# Display.net
KiCad netlist of a schematic drawn in Altium Designer
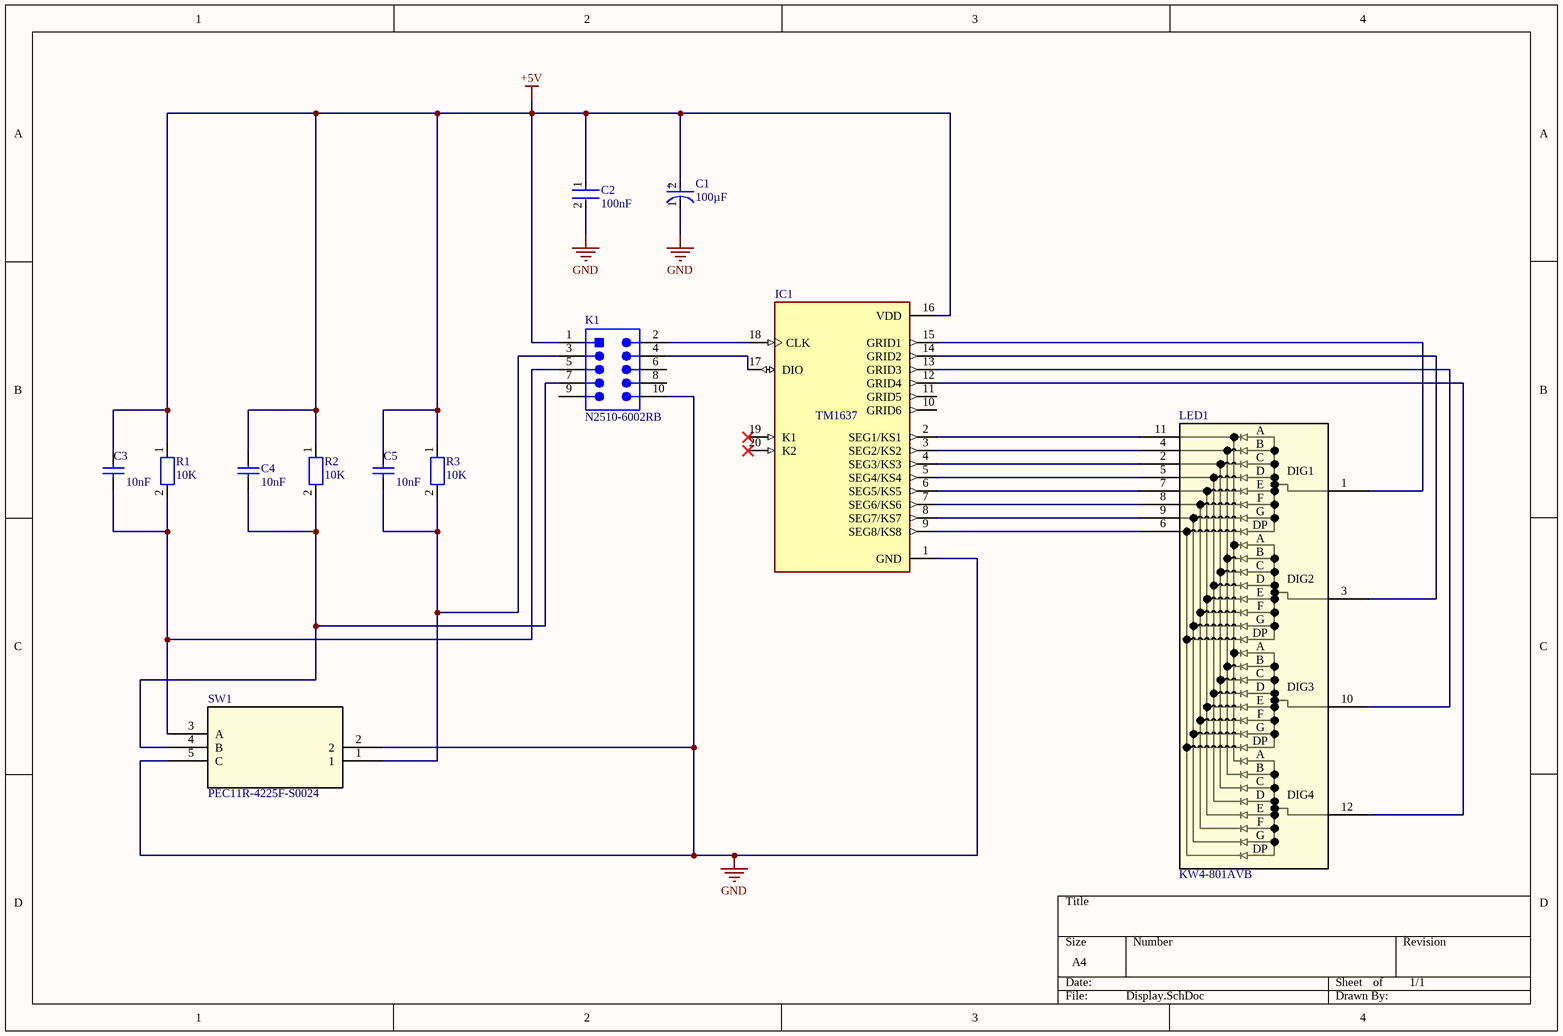
[diagram p0: Display.SchDoc]

(export (version "E")
  (design (tool "Eeschema 10.0.6"))
  (components
    (comp (ref "C1")
      (value "100µF")
      (footprint "Cap 50V 100µF 8X11")
      (description "Aluminum Electrolytic Capacitors (Radial Lead Type) AEC-Q200 Qualified 100uF ±20% 50V")
      (fields (field (name "VOLTAGE") "50V") (field (name "TOLERANCE") "20%"))
      (libsource (lib "soldeerstation") (part "Cap 50V 100µF 8x11"))
    )
    (comp (ref "C2")
      (value "100nF")
      (footprint "cap 50V 100nF A")
      (description "Chip Multilayer Ceramic Capacitors for Automotive, 0805, 0.10uF, X7R, 15%, 10%, 50V, Grade 1")
      (fields (field (name "TOLERANCE") "10%"))
      (libsource (lib "soldeerstation") (part "cap 50V 100nF"))
    )
    (comp (ref "C3")
      (value "10nF")
      (footprint "cap 10nF X7R 50V LL")
      (fields (field (name "PART NUMBER") "VJ0805Y103KXACW1BC") (field (name "MANUFACTURER") "Vitramon"))
      (libsource (lib "soldeerstation") (part "cap 10nF X7R 50V"))
    )
    (comp (ref "C4")
      (value "10nF")
      (footprint "cap 10nF X7R 50V LL")
      (fields (field (name "PART NUMBER") "VJ0805Y103KXACW1BC") (field (name "MANUFACTURER") "Vitramon"))
      (libsource (lib "soldeerstation") (part "cap 10nF X7R 50V"))
    )
    (comp (ref "C5")
      (value "10nF")
      (footprint "cap 10nF X7R 50V LL")
      (fields (field (name "PART NUMBER") "VJ0805Y103KXACW1BC") (field (name "MANUFACTURER") "Vitramon"))
      (libsource (lib "soldeerstation") (part "cap 10nF X7R 50V"))
    )
    (comp (ref "IC1")
      (value "TM1637")
      (footprint "TM1637")
      (description "LED Drive Control Special Circuit")
      (fields (field (name "MF") "Titan Micro Electronics"))
      (libsource (lib "soldeerstation") (part "TM1637"))
    )
    (comp (ref "K1")
      (value "N2510-6002RB")
      (footprint "boxheader")
      (fields (field (name "PARTNUMBER") "N2510") (field (name "MANUFACTURER") "3M"))
      (libsource (lib "soldeerstation") (part "boxheader"))
    )
    (comp (ref "LED1")
      (value "KW4-801AVB")
      (footprint "KW4801AVB")
      (description "No Description Available")
      (fields (field (name "COPYRIGHT") "Copyright (C) 2023 Ultra Librarian. All rights reserved."))
      (libsource (lib "soldeerstation") (part "KW4-801AVB"))
    )
    (comp (ref "R1")
      (value "10K")
      (footprint "Weerstand 10k ohm")
      (description "RES Thick Film, 10kΩ, 1%, 0.125W, 100ppm/°C, 0805")
      (fields (field (name "TOLERANCE") "1%"))
      (libsource (lib "soldeerstation") (part "Weerstand 10K ohm"))
    )
    (comp (ref "R2")
      (value "10K")
      (footprint "Weerstand 10k ohm")
      (description "RES Thick Film, 10kΩ, 1%, 0.125W, 100ppm/°C, 0805")
      (fields (field (name "TOLERANCE") "1%"))
      (libsource (lib "soldeerstation") (part "Weerstand 10K ohm"))
    )
    (comp (ref "R3")
      (value "10K")
      (footprint "Weerstand 10k ohm")
      (description "RES Thick Film, 10kΩ, 1%, 0.125W, 100ppm/°C, 0805")
      (fields (field (name "TOLERANCE") "1%"))
      (libsource (lib "soldeerstation") (part "Weerstand 10K ohm"))
    )
    (comp (ref "SW1")
      (value "PEC11R-4225F-S0024")
      (footprint "SW5_PEC11R-4225F-S0024_BRN")
      (description "No Description Available")
      (fields (field (name "COPYRIGHT") "Copyright (C) 2023 Ultra Librarian. All rights reserved."))
      (libsource (lib "soldeerstation") (part "PEC11R-4225F-S0024"))
    )
  )
  (nets
    (net (code "1") (name "+5V") (class "Default")
      (node (ref "C1") (pin "2") (pinfunction "A_2") (pintype "passive"))
      (node (ref "C2") (pin "1") (pinfunction "1_1") (pintype "passive"))
      (node (ref "C3") (pin "2") (pinfunction "2_2") (pintype "passive"))
      (node (ref "C4") (pin "2") (pinfunction "2_2") (pintype "passive"))
      (node (ref "C5") (pin "2") (pinfunction "2_2") (pintype "passive"))
      (node (ref "IC1") (pin "16") (pinfunction "VDD_16") (pintype "power_in"))
      (node (ref "K1") (pin "1") (pinfunction "1_1") (pintype "passive"))
      (node (ref "R1") (pin "1") (pinfunction "1_1") (pintype "passive"))
      (node (ref "R2") (pin "1") (pinfunction "1_1") (pintype "passive"))
      (node (ref "R3") (pin "1") (pinfunction "1_1") (pintype "passive"))
    )
    (net (code "2") (name "GND") (class "Default")
      (node (ref "C1") (pin "1") (pinfunction "C_1") (pintype "passive"))
      (node (ref "C2") (pin "2") (pinfunction "2_2") (pintype "passive"))
      (node (ref "IC1") (pin "1") (pinfunction "GND_1") (pintype "power_in"))
      (node (ref "K1") (pin "10") (pinfunction "10_10") (pintype "passive"))
      (node (ref "SW1") (pin "2") (pinfunction "2_2") (pintype "passive"))
      (node (ref "SW1") (pin "5") (pinfunction "C_5") (pintype "passive"))
    )
    (net (code "3") (name "Net-(C5-Pad1)") (class "Default")
      (node (ref "C5") (pin "1") (pinfunction "1_1") (pintype "passive"))
      (node (ref "K1") (pin "3") (pinfunction "3_3") (pintype "passive"))
      (node (ref "R3") (pin "2") (pinfunction "2_2") (pintype "passive"))
      (node (ref "SW1") (pin "1") (pinfunction "1_1") (pintype "passive"))
    )
    (net (code "4") (name "Net-(IC1-CLK)") (class "Default")
      (node (ref "IC1") (pin "18") (pinfunction "CLK_18") (pintype "input"))
      (node (ref "K1") (pin "2") (pinfunction "2_2") (pintype "passive"))
    )
    (net (code "5") (name "Net-(IC1-DIO)") (class "Default")
      (node (ref "IC1") (pin "17") (pinfunction "DIO_17") (pintype "bidirectional"))
      (node (ref "K1") (pin "4") (pinfunction "4_4") (pintype "passive"))
    )
    (net (code "6") (name "Net-(IC1-GRID1)") (class "Default")
      (node (ref "IC1") (pin "15") (pinfunction "GRID1_15") (pintype "output"))
      (node (ref "LED1") (pin "1") (pinfunction "COMMON_ANODE_1_1") (pintype "passive"))
    )
    (net (code "7") (name "Net-(IC1-GRID2)") (class "Default")
      (node (ref "IC1") (pin "14") (pinfunction "GRID2_14") (pintype "output"))
      (node (ref "LED1") (pin "3") (pinfunction "COMMON_ANODE_2_3") (pintype "passive"))
    )
    (net (code "8") (name "Net-(IC1-GRID3)") (class "Default")
      (node (ref "IC1") (pin "13") (pinfunction "GRID3_13") (pintype "output"))
      (node (ref "LED1") (pin "10") (pinfunction "COMMON_ANODE_3_10") (pintype "passive"))
    )
    (net (code "9") (name "Net-(IC1-GRID4)") (class "Default")
      (node (ref "IC1") (pin "12") (pinfunction "GRID4_12") (pintype "output"))
      (node (ref "LED1") (pin "12") (pinfunction "COMMON_ANODE_4_12") (pintype "passive"))
    )
    (net (code "10") (name "Net-(IC1-SEG1{slash}KS1)") (class "Default")
      (node (ref "IC1") (pin "2") (pinfunction "SEG1/KS1_2") (pintype "output"))
      (node (ref "LED1") (pin "11") (pinfunction "CATHODE_A_11") (pintype "passive"))
    )
    (net (code "11") (name "Net-(IC1-SEG2{slash}KS2)") (class "Default")
      (node (ref "IC1") (pin "3") (pinfunction "SEG2/KS2_3") (pintype "output"))
      (node (ref "LED1") (pin "4") (pinfunction "CATHODE_B_4") (pintype "passive"))
    )
    (net (code "12") (name "Net-(IC1-SEG3{slash}KS3)") (class "Default")
      (node (ref "IC1") (pin "4") (pinfunction "SEG3/KS3_4") (pintype "output"))
      (node (ref "LED1") (pin "2") (pinfunction "CATHODE_C_2") (pintype "passive"))
    )
    (net (code "13") (name "Net-(IC1-SEG4{slash}KS4)") (class "Default")
      (node (ref "IC1") (pin "5") (pinfunction "SEG4/KS4_5") (pintype "output"))
      (node (ref "LED1") (pin "5") (pinfunction "CATHODE_D_5") (pintype "passive"))
    )
    (net (code "14") (name "Net-(IC1-SEG5{slash}KS5)") (class "Default")
      (node (ref "IC1") (pin "6") (pinfunction "SEG5/KS5_6") (pintype "output"))
      (node (ref "LED1") (pin "7") (pinfunction "CATHODE_E_7") (pintype "passive"))
    )
    (net (code "15") (name "Net-(IC1-SEG6{slash}KS6)") (class "Default")
      (node (ref "IC1") (pin "7") (pinfunction "SEG6/KS6_7") (pintype "output"))
      (node (ref "LED1") (pin "8") (pinfunction "CATHODE_F_8") (pintype "passive"))
    )
    (net (code "16") (name "Net-(IC1-SEG7{slash}KS7)") (class "Default")
      (node (ref "IC1") (pin "8") (pinfunction "SEG7/KS7_8") (pintype "output"))
      (node (ref "LED1") (pin "9") (pinfunction "CATHODE_G_9") (pintype "passive"))
    )
    (net (code "17") (name "Net-(IC1-SEG8{slash}KS8)") (class "Default")
      (node (ref "IC1") (pin "9") (pinfunction "SEG8/KS8_9") (pintype "output"))
      (node (ref "LED1") (pin "6") (pinfunction "CATHODE_DP_6") (pintype "passive"))
    )
    (net (code "18") (name "Net-(SW1-A)") (class "Default")
      (node (ref "C3") (pin "1") (pinfunction "1_1") (pintype "passive"))
      (node (ref "K1") (pin "5") (pinfunction "5_5") (pintype "passive"))
      (node (ref "R1") (pin "2") (pinfunction "2_2") (pintype "passive"))
      (node (ref "SW1") (pin "3") (pinfunction "A_3") (pintype "passive"))
    )
    (net (code "19") (name "Net-(SW1-B)") (class "Default")
      (node (ref "C4") (pin "1") (pinfunction "1_1") (pintype "passive"))
      (node (ref "K1") (pin "7") (pinfunction "7_7") (pintype "passive"))
      (node (ref "R2") (pin "2") (pinfunction "2_2") (pintype "passive"))
      (node (ref "SW1") (pin "4") (pinfunction "B_4") (pintype "passive"))
    )
    (net (code "20") (name "unconnected-(IC1-GRID5-Pad11)") (class "Default")
      (node (ref "IC1") (pin "11") (pinfunction "GRID5_11") (pintype "output"))
    )
    (net (code "21") (name "unconnected-(IC1-GRID6-Pad10)") (class "Default")
      (node (ref "IC1") (pin "10") (pinfunction "GRID6_10") (pintype "output"))
    )
    (net (code "22") (name "unconnected-(IC1-K1-Pad19)") (class "Default")
      (node (ref "IC1") (pin "19") (pinfunction "K1_19") (pintype "input+no_connect"))
    )
    (net (code "23") (name "unconnected-(IC1-K2-Pad20)") (class "Default")
      (node (ref "IC1") (pin "20") (pinfunction "K2_20") (pintype "input+no_connect"))
    )
    (net (code "24") (name "unconnected-(K1-Pad6)") (class "Default")
      (node (ref "K1") (pin "6") (pinfunction "6_6") (pintype "passive"))
    )
    (net (code "25") (name "unconnected-(K1-Pad8)") (class "Default")
      (node (ref "K1") (pin "8") (pinfunction "8_8") (pintype "passive"))
    )
    (net (code "26") (name "unconnected-(K1-Pad9)") (class "Default")
      (node (ref "K1") (pin "9") (pinfunction "9_9") (pintype "passive"))
    )
  )
)
